# Current_Sense.net
KiCad netlist of a schematic drawn in Altium Designer
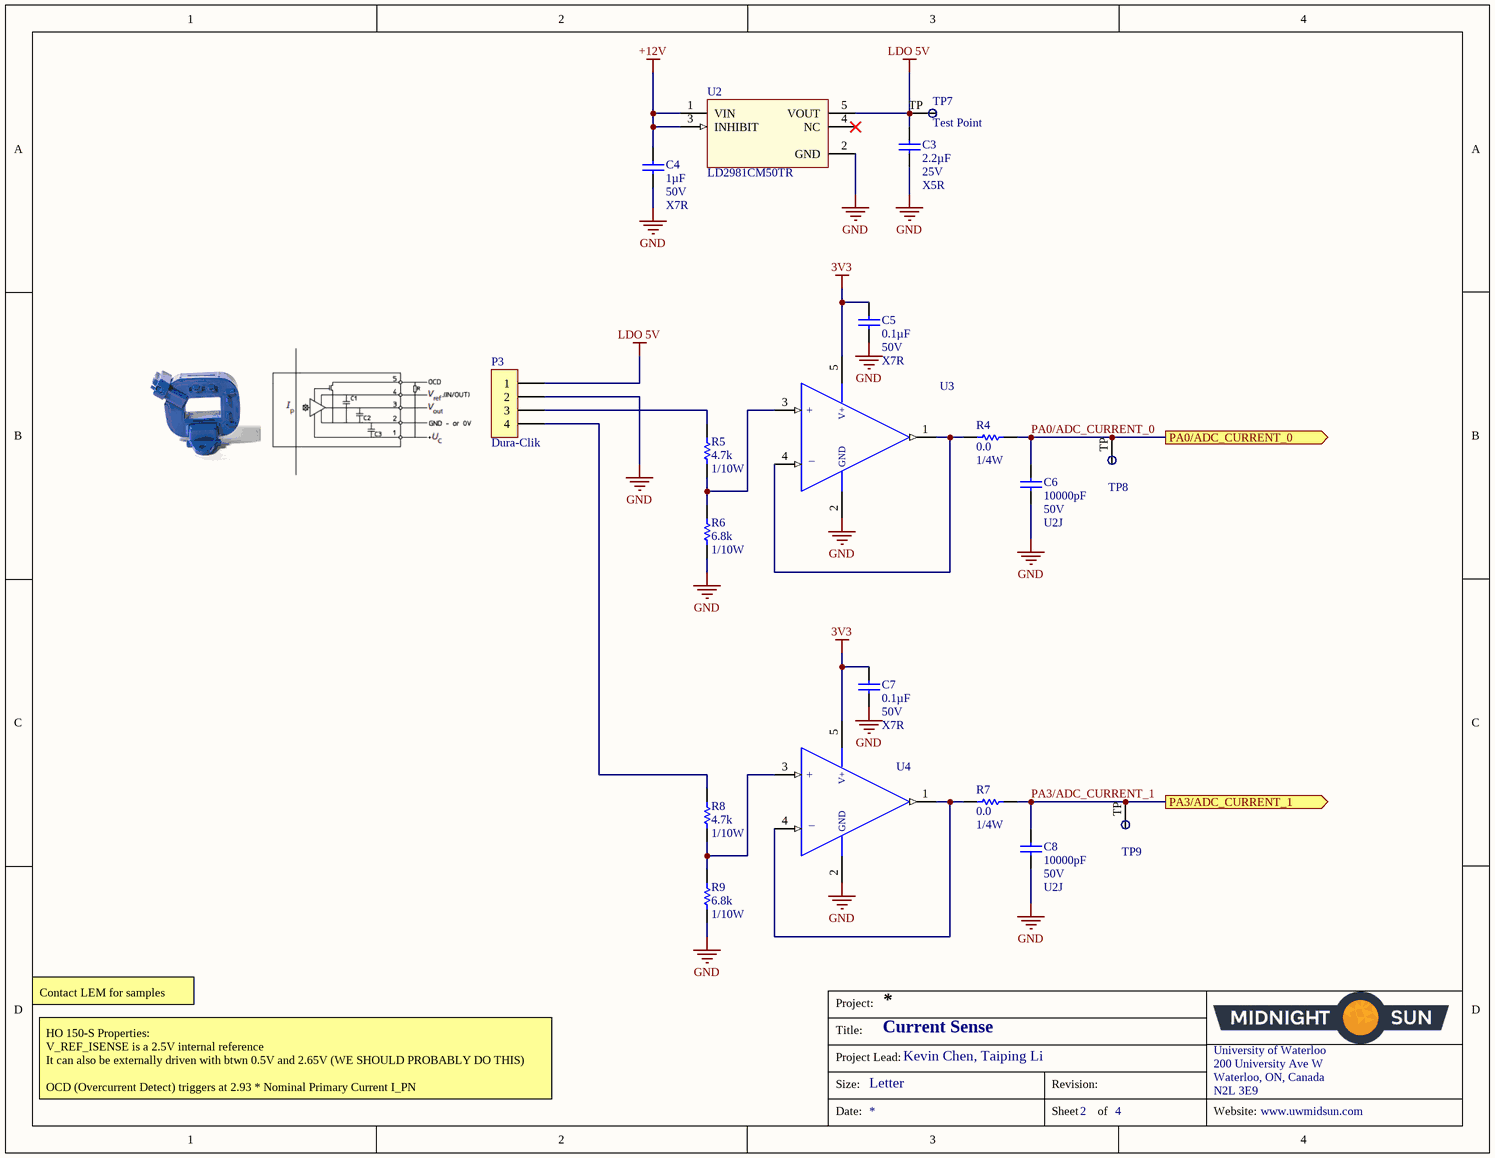
[diagram p0: Current_Sense.SchDoc]

(export (version "E")
  (design (tool "Eeschema 10.0.6"))
  (components
    (comp (ref "C3")
      (value "CAP CER 2.2UF 25V 10% X5R 0603")
      (footprint "CAP, 0603")
      (description "2.2µF ±10% 25V Ceramic Capacitor X5R 0603 (1608 Metric)")
      (fields
        (field (name "TOLERANCE") "±10%")
        (field (name "CAPACITANCE") "2.2µF")
        (field (name "VOLTAGE") "25V")
        (field (name "TEMPERATURE COEFFICIENT") "X5R")
      )
      (libsource (lib "Schematic Diagrams") (part "CAP CER 2.2UF 25V 10% X5R 0603"))
    )
    (comp (ref "C4")
      (value "CAP CER 1UF 50V 10% X7R 0603")
      (footprint "CAP, 0603")
      (description "1µF ±10% 50V Ceramic Capacitor X7R 0603 (1608 Metric)")
      (fields
        (field (name "TOLERANCE") "±10%")
        (field (name "CAPACITANCE") "1µF")
        (field (name "VOLTAGE") "50V")
        (field (name "TEMPERATURE COEFFICIENT") "X7R")
      )
      (libsource (lib "Schematic Diagrams") (part "CAP CER 1UF 50V 10% X7R 0603"))
    )
    (comp (ref "C5")
      (value "CAP CER 0.1UF 50V 10% X7R 0603")
      (footprint "CAP, 0603")
      (description "0.10µF ±10% 50V Ceramic Capacitor X7R 0603 (1608 Metric)")
      (fields
        (field (name "TOLERANCE") "±10%")
        (field (name "CAPACITANCE") "0.1µF")
        (field (name "VOLTAGE") "50V")
        (field (name "TEMPERATURE COEFFICIENT") "X7R")
      )
      (libsource (lib "Schematic Diagrams") (part "CAP CER 0.1UF 50V 10% X7R 0603"))
    )
    (comp (ref "C6")
      (value "CAP CER 10nF 50V 5% X7R 0603")
      (footprint "CAP, 0603")
      (description "10000pF ±5% 50V Ceramic Capacitor U2J 0603 (1608 Metric)")
      (fields
        (field (name "TOLERANCE") "±5%")
        (field (name "CAPACITANCE") "10000pF")
        (field (name "VOLTAGE") "50V")
        (field (name "TEMPERATURE COEFFICIENT") "U2J")
      )
      (libsource (lib "Schematic Diagrams") (part "CAP CER 10nF 50V 5% X7R 0603"))
    )
    (comp (ref "C7")
      (value "CAP CER 0.1UF 50V 10% X7R 0603")
      (footprint "CAP, 0603")
      (description "0.10µF ±10% 50V Ceramic Capacitor X7R 0603 (1608 Metric)")
      (fields
        (field (name "TOLERANCE") "±10%")
        (field (name "CAPACITANCE") "0.1µF")
        (field (name "VOLTAGE") "50V")
        (field (name "TEMPERATURE COEFFICIENT") "X7R")
      )
      (libsource (lib "Schematic Diagrams") (part "CAP CER 0.1UF 50V 10% X7R 0603"))
    )
    (comp (ref "C8")
      (value "CAP CER 10nF 50V 5% X7R 0603")
      (footprint "CAP, 0603")
      (description "10000pF ±5% 50V Ceramic Capacitor U2J 0603 (1608 Metric)")
      (fields
        (field (name "TOLERANCE") "±5%")
        (field (name "CAPACITANCE") "10000pF")
        (field (name "VOLTAGE") "50V")
        (field (name "TEMPERATURE COEFFICIENT") "U2J")
      )
      (libsource (lib "Schematic Diagrams") (part "CAP CER 10nF 50V 5% X7R 0603"))
    )
    (comp (ref "P3")
      (value "Dura-Clik")
      (footprint "CONN, 4POS DURA-CLIK VERT")
      (description "4 Positions Header Connector 0.079\" (2.00mm) Surface Mount Tin")
      (fields
        (field (name "MANUFACTURER") "Molex, LLC")
        (field (name "MANUFACTURER PART NUMBER") "5600200420")
      )
      (libsource (lib "Schematic Diagrams") (part "CONN 4POS DURA-CLIK 0.079{dblquote}"))
    )
    (comp (ref "R4")
      (value "RES 0.0 OHM 1/4W 0603")
      (footprint "RES, 0603")
      (description "RES SMD 0.0 OHM JUMPER 1/4W 0603")
      (fields (field (name "RESISTANCE") "0.0") (field (name "POWER (WATTS)") "1/4W"))
      (libsource (lib "Schematic Diagrams") (part "RES 0.0 OHM 1/4W 0603"))
    )
    (comp (ref "R5")
      (value "RES 4.7K OHM 1% 1/10W 0603")
      (footprint "RES, 0603")
      (description "4.7k Ohm ±1% 0.1W, 1/10W Chip Resistor 0603 (1608 Metric) Moisture Resistant Thick Film")
      (fields
        (field (name "TOLERANCE") "±1%")
        (field (name "RESISTANCE (OHMS)") "4.7k")
        (field (name "POWER (WATTS)") "1/10W")
      )
      (libsource (lib "Schematic Diagrams") (part "RES 4.7K OHM 1% 1/10W 0603"))
    )
    (comp (ref "R6")
      (value "RES 6.8k OHM 1% 1/10W 0603")
      (footprint "RES, 0603")
      (description "RES SMD 6.8K OHM 1% 1/10W 0603")
      (fields
        (field (name "TOLERANCE") "±1%")
        (field (name "RESISTANCE") "6.8k")
        (field (name "POWER") "1/10W")
      )
      (libsource (lib "Schematic Diagrams") (part "RES 6.8k OHM 1% 1/10W 0603"))
    )
    (comp (ref "R7")
      (value "RES 0.0 OHM 1/4W 0603")
      (footprint "RES, 0603")
      (description "RES SMD 0.0 OHM JUMPER 1/4W 0603")
      (fields (field (name "RESISTANCE") "0.0") (field (name "POWER (WATTS)") "1/4W"))
      (libsource (lib "Schematic Diagrams") (part "RES 0.0 OHM 1/4W 0603"))
    )
    (comp (ref "R8")
      (value "RES 4.7K OHM 1% 1/10W 0603")
      (footprint "RES, 0603")
      (description "4.7k Ohm ±1% 0.1W, 1/10W Chip Resistor 0603 (1608 Metric) Moisture Resistant Thick Film")
      (fields
        (field (name "TOLERANCE") "±1%")
        (field (name "RESISTANCE (OHMS)") "4.7k")
        (field (name "POWER (WATTS)") "1/10W")
      )
      (libsource (lib "Schematic Diagrams") (part "RES 4.7K OHM 1% 1/10W 0603"))
    )
    (comp (ref "R9")
      (value "RES 6.8k OHM 1% 1/10W 0603")
      (footprint "RES, 0603")
      (description "RES SMD 6.8K OHM 1% 1/10W 0603")
      (fields
        (field (name "TOLERANCE") "±1%")
        (field (name "RESISTANCE") "6.8k")
        (field (name "POWER") "1/10W")
      )
      (libsource (lib "Schematic Diagrams") (part "RES 6.8k OHM 1% 1/10W 0603"))
    )
    (comp (ref "TP7")
      (value "Test Point")
      (footprint "Test Point")
      (libsource (lib "Schematic Diagrams") (part "Test Point"))
    )
    (comp (ref "TP8")
      (value "Test Point")
      (footprint "Test Point")
      (libsource (lib "Schematic Diagrams") (part "Test Point"))
    )
    (comp (ref "TP9")
      (value "Test Point")
      (footprint "Test Point")
      (libsource (lib "Schematic Diagrams") (part "Test Point"))
    )
    (comp (ref "U2")
      (value "IC REG LDO 5V 0.1A SOT23-5")
      (footprint "SOT95P280X145-5N")
      (description "Linear Voltage Regulator IC Positive Fixed Output 5V 100mA SOT-23-5")
      (fields (field (name "MANUFACTURER PART NUMBER 1") "LD2981CM50TR"))
      (libsource (lib "Schematic Diagrams") (part "IC REG LDO 5V 0.1A SOT23-5"))
    )
    (comp (ref "U3")
      (value "IC OP AMP GEN PURPOSE RR 10MHZ SOT-23-5")
      (footprint "IC OP AMP GP RR 10MHZ SOT-23-5")
      (description "General Purpose Amplifier 1 Circuit Rail-to-Rail SOT-23-5")
      (libsource (lib "Schematic Diagrams") (part "IC OP AMP GEN PURPOSE RR 10MHZ SOT-23-5"))
    )
    (comp (ref "U4")
      (value "IC OP AMP GEN PURPOSE RR 10MHZ SOT-23-5")
      (footprint "IC OP AMP GP RR 10MHZ SOT-23-5")
      (description "General Purpose Amplifier 1 Circuit Rail-to-Rail SOT-23-5")
      (libsource (lib "Schematic Diagrams") (part "IC OP AMP GEN PURPOSE RR 10MHZ SOT-23-5"))
    )
  )
  (nets
    (net (code "1") (name "+12V") (class "Default")
      (node (ref "C4") (pin "1") (pinfunction "1_1") (pintype "passive"))
      (node (ref "U2") (pin "1") (pinfunction "VIN_1") (pintype "power_in"))
      (node (ref "U2") (pin "3") (pinfunction "INHIBIT_3") (pintype "input"))
    )
    (net (code "2") (name "/PA0{slash}ADC_CURRENT_0") (class "Default")
      (node (ref "C6") (pin "1") (pinfunction "1_1") (pintype "passive"))
      (node (ref "R4") (pin "2") (pinfunction "2_2") (pintype "passive"))
      (node (ref "TP8") (pin "TP") (pinfunction "1_TP") (pintype "passive"))
    )
    (net (code "3") (name "/PA3{slash}ADC_CURRENT_1") (class "Default")
      (node (ref "C8") (pin "1") (pinfunction "1_1") (pintype "passive"))
      (node (ref "R7") (pin "2") (pinfunction "2_2") (pintype "passive"))
      (node (ref "TP9") (pin "TP") (pinfunction "1_TP") (pintype "passive"))
    )
    (net (code "4") (name "3V3") (class "Default")
      (node (ref "C5") (pin "1") (pinfunction "1_1") (pintype "passive"))
      (node (ref "C7") (pin "1") (pinfunction "1_1") (pintype "passive"))
      (node (ref "U3") (pin "5") (pinfunction "VDD_5") (pintype "power_in"))
      (node (ref "U4") (pin "5") (pinfunction "VDD_5") (pintype "power_in"))
    )
    (net (code "5") (name "GND") (class "Default")
      (node (ref "C3") (pin "2") (pinfunction "2_2") (pintype "passive"))
      (node (ref "C4") (pin "2") (pinfunction "2_2") (pintype "passive"))
      (node (ref "C5") (pin "2") (pinfunction "2_2") (pintype "passive"))
      (node (ref "C6") (pin "2") (pinfunction "2_2") (pintype "passive"))
      (node (ref "C7") (pin "2") (pinfunction "2_2") (pintype "passive"))
      (node (ref "C8") (pin "2") (pinfunction "2_2") (pintype "passive"))
      (node (ref "P3") (pin "2") (pinfunction "2_2") (pintype "passive"))
      (node (ref "R6") (pin "2") (pinfunction "2_2") (pintype "passive"))
      (node (ref "R9") (pin "2") (pinfunction "2_2") (pintype "passive"))
      (node (ref "U2") (pin "2") (pinfunction "GND_2") (pintype "power_in"))
      (node (ref "U3") (pin "2") (pinfunction "VSS_2") (pintype "power_in"))
      (node (ref "U4") (pin "2") (pinfunction "VSS_2") (pintype "power_in"))
    )
    (net (code "6") (name "LDO 5V") (class "Default")
      (node (ref "C3") (pin "1") (pinfunction "1_1") (pintype "passive"))
      (node (ref "P3") (pin "1") (pinfunction "1_1") (pintype "passive"))
      (node (ref "TP7") (pin "TP") (pinfunction "1_TP") (pintype "passive"))
      (node (ref "U2") (pin "5") (pinfunction "VOUT_5") (pintype "power_in"))
    )
    (net (code "7") (name "Net-(P3-Pad3)") (class "Default")
      (node (ref "P3") (pin "3") (pinfunction "3_3") (pintype "passive"))
      (node (ref "R5") (pin "1") (pinfunction "1_1") (pintype "passive"))
    )
    (net (code "8") (name "Net-(P3-Pad4)") (class "Default")
      (node (ref "P3") (pin "4") (pinfunction "4_4") (pintype "passive"))
      (node (ref "R8") (pin "1") (pinfunction "1_1") (pintype "passive"))
    )
    (net (code "9") (name "Net-(U3-+IN)") (class "Default")
      (node (ref "R5") (pin "2") (pinfunction "2_2") (pintype "passive"))
      (node (ref "R6") (pin "1") (pinfunction "1_1") (pintype "passive"))
      (node (ref "U3") (pin "3") (pinfunction "+IN_3") (pintype "input"))
    )
    (net (code "10") (name "Net-(U3--IN)") (class "Default")
      (node (ref "R4") (pin "1") (pinfunction "1_1") (pintype "passive"))
      (node (ref "U3") (pin "1") (pinfunction "OUTPUT_1") (pintype "output"))
      (node (ref "U3") (pin "4") (pinfunction "-IN_4") (pintype "input"))
    )
    (net (code "11") (name "Net-(U4-+IN)") (class "Default")
      (node (ref "R8") (pin "2") (pinfunction "2_2") (pintype "passive"))
      (node (ref "R9") (pin "1") (pinfunction "1_1") (pintype "passive"))
      (node (ref "U4") (pin "3") (pinfunction "+IN_3") (pintype "input"))
    )
    (net (code "12") (name "Net-(U4--IN)") (class "Default")
      (node (ref "R7") (pin "1") (pinfunction "1_1") (pintype "passive"))
      (node (ref "U4") (pin "1") (pinfunction "OUTPUT_1") (pintype "output"))
      (node (ref "U4") (pin "4") (pinfunction "-IN_4") (pintype "input"))
    )
    (net (code "13") (name "unconnected-(U2-NC-Pad4)") (class "Default")
      (node (ref "U2") (pin "4") (pinfunction "NC_4") (pintype "passive+no_connect"))
    )
  )
)
